# diagnostic_tool.net
KiCad netlist of a schematic drawn in EAGLE
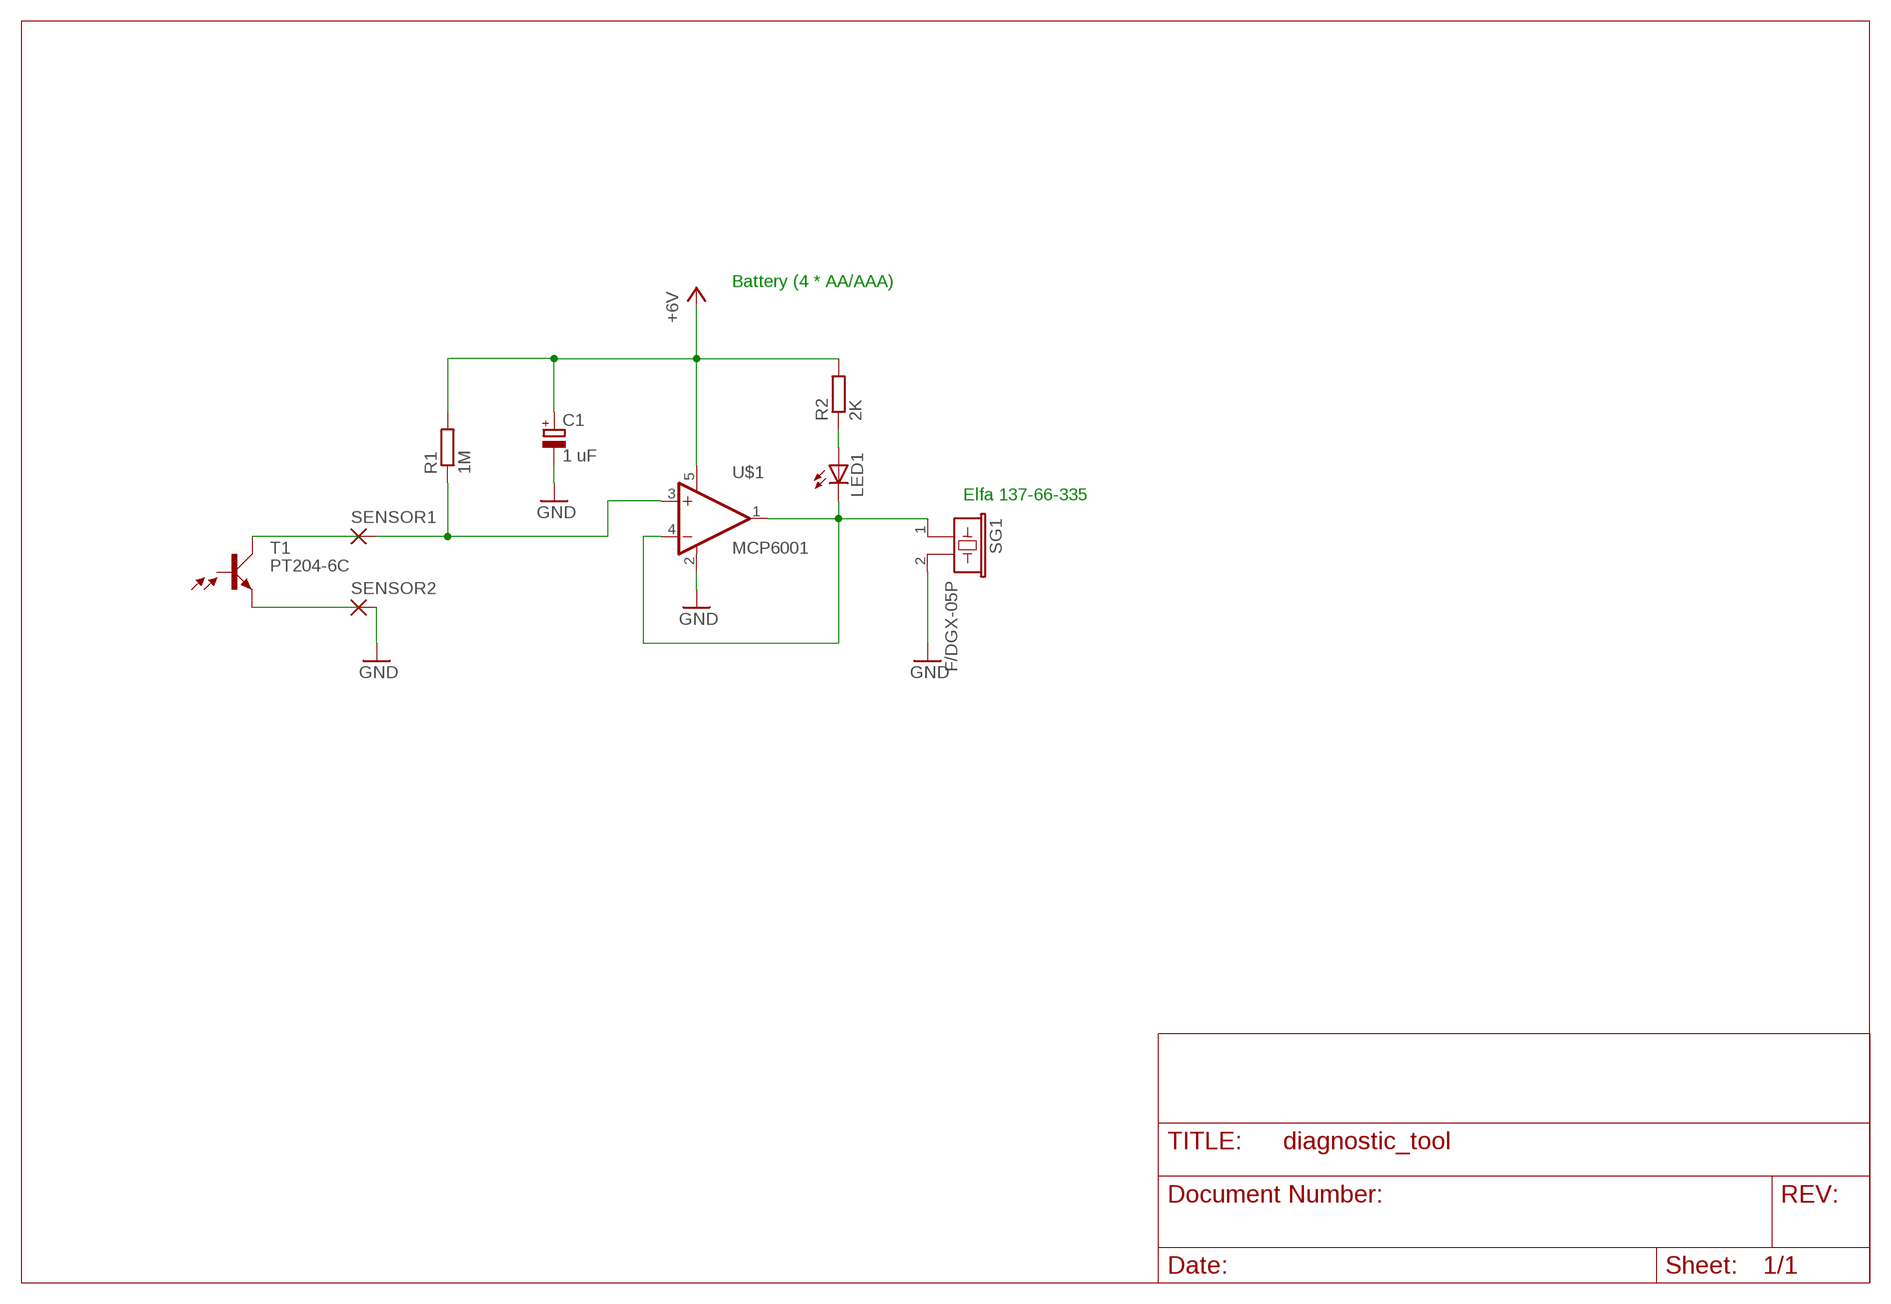
[diagram p0: schematic, sheet 1]

(export (version "E")
  (design (tool "Eeschema 10.0.6"))
  (components
    (comp (ref "C1")
      (value "1 uF")
      (footprint "eagle-import:E2,5-5")
      (libsource (lib "eagle-import") (part "CPOL-EUE2.5-5"))
    )
    (comp (ref "LED1")
      (value "LED")
      (footprint "eagle-import:SMARTLED-TTW")
      (libsource (lib "eagle-import") (part "LED"))
    )
    (comp (ref "R1")
      (value "1M")
      (footprint "eagle-import:0207_10")
      (libsource (lib "eagle-import") (part "R-EU_0207/10"))
    )
    (comp (ref "R2")
      (value "2K")
      (footprint "eagle-import:0207_10")
      (libsource (lib "eagle-import") (part "R-EU_0207/10"))
    )
    (comp (ref "SENSOR1")
      (value "WIREPAD1,6/0,8")
      (footprint "eagle-import:1,6_0,8")
      (libsource (lib "eagle-import") (part "WIREPAD1,6/0,8"))
    )
    (comp (ref "SENSOR2")
      (value "WIREPAD1,6/0,8")
      (footprint "eagle-import:1,6_0,8")
      (libsource (lib "eagle-import") (part "WIREPAD1,6/0,8"))
    )
    (comp (ref "SG1")
      (value "F/DGX-05P")
      (footprint "eagle-import:B_C11L")
      (libsource (lib "eagle-import") (part "B/C11L"))
    )
    (comp (ref "T1")
      (value "PT204-6C")
      (footprint "eagle-import:BP103")
      (libsource (lib "eagle-import") (part "BP103"))
    )
    (comp (ref "U$1")
      (value "MCP6001")
      (footprint "eagle-import:SOT23-5L")
      (libsource (lib "eagle-import") (part "MCP6001"))
    )
  )
  (nets
    (net (code "1") (name "+6V") (class "Default")
      (node (ref "C1") (pin "+") (pinfunction "+_+") (pintype "passive"))
      (node (ref "R1") (pin "2") (pinfunction "2_2") (pintype "passive"))
      (node (ref "R2") (pin "2") (pinfunction "2_2") (pintype "passive"))
      (node (ref "U$1") (pin "5") (pinfunction "V+_5") (pintype "power_in"))
    )
    (net (code "2") (name "GND") (class "Default")
      (node (ref "C1") (pin "-") (pinfunction "-_-") (pintype "passive"))
      (node (ref "SENSOR2") (pin "1") (pinfunction "P_1") (pintype "passive"))
      (node (ref "SG1") (pin "2") (pinfunction "2_2") (pintype "passive"))
      (node (ref "U$1") (pin "2") (pinfunction "V-_2") (pintype "power_in"))
    )
    (net (code "3") (name "Net-(LED1-A)") (class "Default")
      (node (ref "LED1") (pin "A@1") (pinfunction "A_A@1") (pintype "passive"))
      (node (ref "R2") (pin "1") (pinfunction "1_1") (pintype "passive"))
    )
    (net (code "4") (name "Net-(LED1-C)") (class "Default")
      (node (ref "LED1") (pin "C@1") (pinfunction "C_C@1") (pintype "passive"))
      (node (ref "SG1") (pin "1") (pinfunction "1_1") (pintype "passive"))
      (node (ref "U$1") (pin "1") (pinfunction "OUT_1") (pintype "output"))
      (node (ref "U$1") (pin "4") (pinfunction "-IN_4") (pintype "input"))
    )
    (net (code "5") (name "Net-(SENSOR1-P)") (class "Default")
      (node (ref "R1") (pin "1") (pinfunction "1_1") (pintype "passive"))
      (node (ref "SENSOR1") (pin "1") (pinfunction "P_1") (pintype "passive"))
      (node (ref "U$1") (pin "3") (pinfunction "+IN_3") (pintype "input"))
    )
    (net (code "6") (name "unconnected-(T1-PadB)") (class "Default")
      (node (ref "T1") (pin "B") (pinfunction "B_B") (pintype "passive"))
    )
    (net (code "7") (name "unconnected-(T1-PadC)") (class "Default")
      (node (ref "T1") (pin "C") (pinfunction "C_C") (pintype "passive"))
    )
    (net (code "8") (name "unconnected-(T1-PadE)") (class "Default")
      (node (ref "T1") (pin "E") (pinfunction "E_E") (pintype "passive"))
    )
  )
)
